# POWER_SUPPLY.net
KiCad netlist of a schematic drawn in Altium Designer
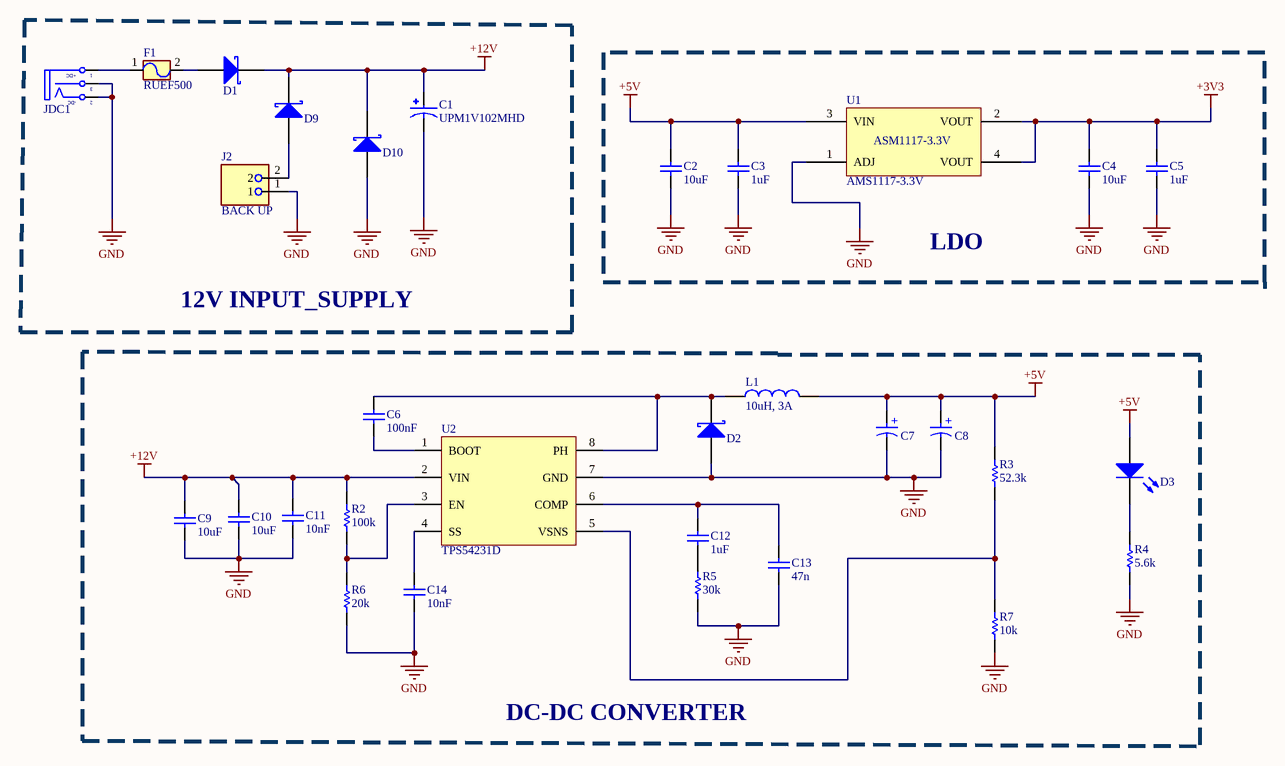
[diagram p0: POWER SUPPLY.SchDoc]

(export (version "E")
  (design (tool "Eeschema 10.0.6"))
  (components
    (comp (ref "C1")
      (value "UPM1V102MHD")
      (footprint "CAPPRD500W80D1250H3350")
      (fields (field (name "MF") "Nichicon"))
      (libsource (lib "UPM1V102MHD") (part "UPM1V102MHD"))
    )
    (comp (ref "C2")
      (value "10uF")
      (footprint "CAP_0603")
      (description "CAP, size 0603, 1uF")
      (libsource (lib "SMIOT_Lib_Schematic") (part "01060310510"))
    )
    (comp (ref "C3")
      (value "1uF")
      (footprint "CAP_0603")
      (description "CAP, size 0603, 100nF")
      (libsource (lib "SMIOT_Lib_Schematic") (part "01060310410"))
    )
    (comp (ref "C4")
      (value "10uF")
      (footprint "CAP_0603")
      (description "CAP, size 0603, 1uF")
      (libsource (lib "SMIOT_Lib_Schematic") (part "01060310510"))
    )
    (comp (ref "C5")
      (value "1uF")
      (footprint "CAP_0603")
      (description "CAP, size 0603, 100nF")
      (libsource (lib "SMIOT_Lib_Schematic") (part "01060310410"))
    )
    (comp (ref "C6")
      (value "100nF")
      (footprint "CAP_0603")
      (description "CAP, size 0603, 100nF")
      (libsource (lib "SMIOT_Lib_Schematic") (part "01060310410"))
    )
    (comp (ref "C7")
      (value "47uF")
      (footprint "WCAP-ASLI_D5H5.5")
      (description "V-Chip, D5 x H5.5mm, 47uF, 16V")
      (libsource (lib "SMIOT_Lib_Schematic") (part "865080342006"))
    )
    (comp (ref "C8")
      (value "47uF")
      (footprint "WCAP-ASLI_D5H5.5")
      (description "V-Chip, D5 x H5.5mm, 47uF, 16V")
      (libsource (lib "SMIOT_Lib_Schematic") (part "865080342006"))
    )
    (comp (ref "C9")
      (value "10uF")
      (footprint "CAP_0603")
      (description "CAP, size 0603,10uF")
      (libsource (lib "SMIOT_Lib_Schematic") (part "01060310010"))
    )
    (comp (ref "C10")
      (value "10uF")
      (footprint "CAP_0603")
      (description "CAP, size 0603,10uF")
      (libsource (lib "SMIOT_Lib_Schematic") (part "01060310010"))
    )
    (comp (ref "C11")
      (value "10nF")
      (footprint "CAP_0603")
      (description "CAP, size 0603, 10nF")
      (libsource (lib "SMIOT_Lib_Schematic") (part "01060310310"))
    )
    (comp (ref "C12")
      (value "1uF")
      (footprint "CAP_0603")
      (description "CAP, size 0603, 1uF")
      (libsource (lib "SMIOT_Lib_Schematic") (part "01060310510"))
    )
    (comp (ref "C13")
      (value "47n")
      (footprint "CAP_0603")
      (description "CAP, size 0603, 47nF")
      (libsource (lib "SMIOT_Lib_Schematic") (part "01060347310"))
    )
    (comp (ref "C14")
      (value "10nF")
      (footprint "CAP_0603")
      (description "CAP, size 0603, 10nF")
      (libsource (lib "SMIOT_Lib_Schematic") (part "01060310310"))
    )
    (comp (ref "D1")
      (value "D Schottky")
      (footprint "SS34")
      (description "Schottky Diode SS54A")
      (fields (field (name "PUBLISHER") "Altium Limited"))
      (libsource (lib "Board_C24") (part "D Schottky"))
    )
    (comp (ref "D2")
      (value "D Schottky")
      (footprint "SS34")
      (description "Schottky Diode")
      (fields (field (name "PUBLISHER") "Altium Limited"))
      (libsource (lib "SMIOT_Lib_Schematic") (part "D Schottky"))
    )
    (comp (ref "D3")
      (value "LED SMD")
      (footprint "LED_0805_Blue")
      (description "LED")
      (libsource (lib "SMIOT_Lib_Schematic") (part "LED SMD"))
    )
    (comp (ref "D9")
      (value "D Schottky")
      (footprint "SS34")
      (description "Schottky Diode SS54A")
      (fields (field (name "PUBLISHER") "Altium Limited"))
      (libsource (lib "Board_C24") (part "D Schottky"))
    )
    (comp (ref "D10")
      (value "D Schottky")
      (footprint "SS34")
      (description "Schottky Diode SS54A")
      (fields (field (name "PUBLISHER") "Altium Limited"))
      (libsource (lib "Board_C24") (part "D Schottky"))
    )
    (comp (ref "F1")
      (value "RUEF500")
      (footprint "RUEF400")
      (description "Polymeric PTC Resettable Fuse 30V 5 A Ih Through Hole Radial, Disc")
      (fields (field (name "MF") "Littelfuse"))
      (libsource (lib "RUEF500") (part "RUEF500"))
    )
    (comp (ref "J2")
      (value "BACK UP")
      (footprint "PHOENIX_1935161")
      (description "PCB Terminal Screw 5mm 16AWG 400V 17.5A 2 Position COMBICON PT Series ¦ Phoenix Contact 1935161")
      (fields (field (name "MF") "Phoenix Contact") (field (name "MP") "1935161"))
      (libsource (lib "Domino") (part "Domino"))
    )
    (comp (ref "JDC1")
      (value "Jack DC")
      (footprint "DC-IN")
      (description "Jack DC input")
      (libsource (lib "SMIOT_Lib_Schematic") (part "Jack DC"))
    )
    (comp (ref "L1")
      (value "10uH, 3A")
      (footprint "WE-PD2A_5848")
      (description "WE-PD2A SMT Power Inductor, size 5848, 10uH, 2.2A")
      (fields
        (field (name "MANUFACTURER PART NUMBER") "78477410")
        (field (name "MANUFACTURER") "Wurth Elektronik")
      )
      (libsource (lib "SMIOT_Lib_Schematic") (part "78477410"))
    )
    (comp (ref "R2")
      (value "100k")
      (footprint "resistor_0603")
      (description "RES, 100k Ohm, size 0603, 1%")
      (libsource (lib "SMIOT_Lib_Schematic") (part "0006031041"))
    )
    (comp (ref "R3")
      (value "52.3k")
      (footprint "resistor_0603")
      (description "RES, 52.3 kOhms, size 0603, 1%")
      (libsource (lib "SMIOT_Lib_Schematic") (part "0006038251"))
    )
    (comp (ref "R4")
      (value "5.6k")
      (footprint "resistor_0603")
      (description "RES, 5.6k Ohm, size 0603, 1%")
      (libsource (lib "SMIOT_Lib_Schematic") (part "0006035621"))
    )
    (comp (ref "R5")
      (value "30k")
      (footprint "resistor_0603")
      (description "RES, 30k Ohm, size 0603, 1%")
      (libsource (lib "SMIOT_Lib_Schematic") (part "0006033205"))
    )
    (comp (ref "R6")
      (value "20k")
      (footprint "resistor_0603")
      (description "RES, 20 kOhms, size 0603, 1%")
      (libsource (lib "SMIOT_Lib_Schematic") (part "0006032031"))
    )
    (comp (ref "R7")
      (value "10k")
      (footprint "resistor_0603")
      (description "RES, 1.5 kOhms, size 0603, 1%")
      (libsource (lib "SMIOT_Lib_Schematic") (part "0006031521"))
    )
    (comp (ref "U1")
      (value "AMS1117-3.3V")
      (footprint "AMS1117-3.3V SOT223")
      (description "AMS1117-3.3V, OUT 3.3V 1A.")
      (fields (field (name "MANUFACTURER") "AMS"))
      (libsource (lib "SMIOT_Lib_Schematic") (part "AMS1117-3.3V"))
    )
    (comp (ref "U2")
      (value "TPS54231D")
      (footprint "SOIC8")
      (description "Buck Switching Regulator IC Positive Adjustable 0.8V 1 Output 2A 8-SOIC (0.154\", 3.90mm Width)")
      (fields (field (name "MFR") "Texas Instruments"))
      (libsource (lib "SMIOT_Lib_Schematic") (part "TPS54231"))
    )
  )
  (nets
    (net (code "1") (name "+3V3") (class "Default")
      (node (ref "C4") (pin "2") (pinfunction "2_2") (pintype "passive"))
      (node (ref "C5") (pin "2") (pinfunction "2_2") (pintype "passive"))
      (node (ref "U1") (pin "2") (pinfunction "VOUT_2") (pintype "passive"))
      (node (ref "U1") (pin "4") (pinfunction "VOUT_4") (pintype "power_in"))
    )
    (net (code "2") (name "+5V") (class "Default")
      (node (ref "C2") (pin "2") (pinfunction "2_2") (pintype "passive"))
      (node (ref "C3") (pin "2") (pinfunction "2_2") (pintype "passive"))
      (node (ref "C7") (pin "1") (pinfunction "P_1") (pintype "passive"))
      (node (ref "C8") (pin "1") (pinfunction "P_1") (pintype "passive"))
      (node (ref "D3") (pin "1") (pinfunction "A_1") (pintype "passive"))
      (node (ref "L1") (pin "2") (pinfunction "2_2") (pintype "passive"))
      (node (ref "R3") (pin "2") (pinfunction "2_2") (pintype "passive"))
      (node (ref "U1") (pin "3") (pinfunction "VIN_3") (pintype "passive"))
    )
    (net (code "3") (name "+12V") (class "Default")
      (node (ref "C1") (pin "P") (pinfunction "P_P") (pintype "passive"))
      (node (ref "C10") (pin "2") (pinfunction "2_2") (pintype "passive"))
      (node (ref "C11") (pin "2") (pinfunction "2_2") (pintype "passive"))
      (node (ref "C9") (pin "2") (pinfunction "2_2") (pintype "passive"))
      (node (ref "D1") (pin "2") (pinfunction "K_2") (pintype "passive"))
      (node (ref "D10") (pin "2") (pinfunction "K_2") (pintype "passive"))
      (node (ref "D9") (pin "2") (pinfunction "K_2") (pintype "passive"))
      (node (ref "R2") (pin "2") (pinfunction "2_2") (pintype "passive"))
      (node (ref "U2") (pin "2") (pinfunction "VIN_2") (pintype "passive"))
    )
    (net (code "4") (name "GND") (class "Default")
      (node (ref "C1") (pin "N") (pinfunction "N_N") (pintype "passive"))
      (node (ref "C10") (pin "1") (pinfunction "1_1") (pintype "passive"))
      (node (ref "C11") (pin "1") (pinfunction "1_1") (pintype "passive"))
      (node (ref "C13") (pin "1") (pinfunction "1_1") (pintype "passive"))
      (node (ref "C14") (pin "1") (pinfunction "1_1") (pintype "passive"))
      (node (ref "C2") (pin "1") (pinfunction "1_1") (pintype "passive"))
      (node (ref "C3") (pin "1") (pinfunction "1_1") (pintype "passive"))
      (node (ref "C4") (pin "1") (pinfunction "1_1") (pintype "passive"))
      (node (ref "C5") (pin "1") (pinfunction "1_1") (pintype "passive"))
      (node (ref "C7") (pin "2") (pinfunction "N_2") (pintype "passive"))
      (node (ref "C8") (pin "2") (pinfunction "N_2") (pintype "passive"))
      (node (ref "C9") (pin "1") (pinfunction "1_1") (pintype "passive"))
      (node (ref "D10") (pin "1") (pinfunction "A_1") (pintype "passive"))
      (node (ref "D2") (pin "1") (pinfunction "A_1") (pintype "passive"))
      (node (ref "J2") (pin "1") (pinfunction "1_1") (pintype "passive"))
      (node (ref "JDC1") (pin "2") (pinfunction "TN_2") (pintype "passive"))
      (node (ref "JDC1") (pin "3") (pinfunction "S_3") (pintype "power_in"))
      (node (ref "R4") (pin "1") (pinfunction "1_1") (pintype "passive"))
      (node (ref "R5") (pin "1") (pinfunction "1_1") (pintype "passive"))
      (node (ref "R6") (pin "1") (pinfunction "1_1") (pintype "passive"))
      (node (ref "R7") (pin "1") (pinfunction "1_1") (pintype "passive"))
      (node (ref "U1") (pin "1") (pinfunction "ADJ_1") (pintype "power_in"))
      (node (ref "U2") (pin "7") (pinfunction "GND_7") (pintype "passive"))
    )
    (net (code "5") (name "Net-(C12-Pad2)") (class "Default")
      (node (ref "C12") (pin "2") (pinfunction "2_2") (pintype "passive"))
      (node (ref "R5") (pin "2") (pinfunction "2_2") (pintype "passive"))
    )
    (net (code "6") (name "Net-(D1-A)") (class "Default")
      (node (ref "D1") (pin "1") (pinfunction "A_1") (pintype "passive"))
      (node (ref "F1") (pin "2") (pinfunction "2_2") (pintype "bidirectional"))
    )
    (net (code "7") (name "Net-(D2-K)") (class "Default")
      (node (ref "C6") (pin "2") (pinfunction "2_2") (pintype "passive"))
      (node (ref "D2") (pin "2") (pinfunction "K_2") (pintype "passive"))
      (node (ref "L1") (pin "1") (pinfunction "1_1") (pintype "passive"))
      (node (ref "U2") (pin "8") (pinfunction "PH_8") (pintype "passive"))
    )
    (net (code "8") (name "Net-(D3-K)") (class "Default")
      (node (ref "D3") (pin "2") (pinfunction "K_2") (pintype "passive"))
      (node (ref "R4") (pin "2") (pinfunction "2_2") (pintype "passive"))
    )
    (net (code "9") (name "Net-(D9-A)") (class "Default")
      (node (ref "D9") (pin "1") (pinfunction "A_1") (pintype "passive"))
      (node (ref "J2") (pin "2") (pinfunction "2_2") (pintype "passive"))
    )
    (net (code "10") (name "Net-(JDC1-T)") (class "Default")
      (node (ref "F1") (pin "1") (pinfunction "1_1") (pintype "bidirectional"))
      (node (ref "JDC1") (pin "1") (pinfunction "T_1") (pintype "passive"))
    )
    (net (code "11") (name "Net-(U2-BOOT)") (class "Default")
      (node (ref "C6") (pin "1") (pinfunction "1_1") (pintype "passive"))
      (node (ref "U2") (pin "1") (pinfunction "BOOT_1") (pintype "passive"))
    )
    (net (code "12") (name "Net-(U2-COMP)") (class "Default")
      (node (ref "C12") (pin "1") (pinfunction "1_1") (pintype "passive"))
      (node (ref "C13") (pin "2") (pinfunction "2_2") (pintype "passive"))
      (node (ref "U2") (pin "6") (pinfunction "COMP_6") (pintype "passive"))
    )
    (net (code "13") (name "Net-(U2-EN)") (class "Default")
      (node (ref "R2") (pin "1") (pinfunction "1_1") (pintype "passive"))
      (node (ref "R6") (pin "2") (pinfunction "2_2") (pintype "passive"))
      (node (ref "U2") (pin "3") (pinfunction "EN_3") (pintype "passive"))
    )
    (net (code "14") (name "Net-(U2-SS)") (class "Default")
      (node (ref "C14") (pin "2") (pinfunction "2_2") (pintype "passive"))
      (node (ref "U2") (pin "4") (pinfunction "SS_4") (pintype "passive"))
    )
    (net (code "15") (name "Net-(U2-VSNS)") (class "Default")
      (node (ref "R3") (pin "1") (pinfunction "1_1") (pintype "passive"))
      (node (ref "R7") (pin "2") (pinfunction "2_2") (pintype "passive"))
      (node (ref "U2") (pin "5") (pinfunction "VSNS_5") (pintype "passive"))
    )
  )
)
